# Powerboard.net
KiCad netlist of a schematic drawn in EAGLE
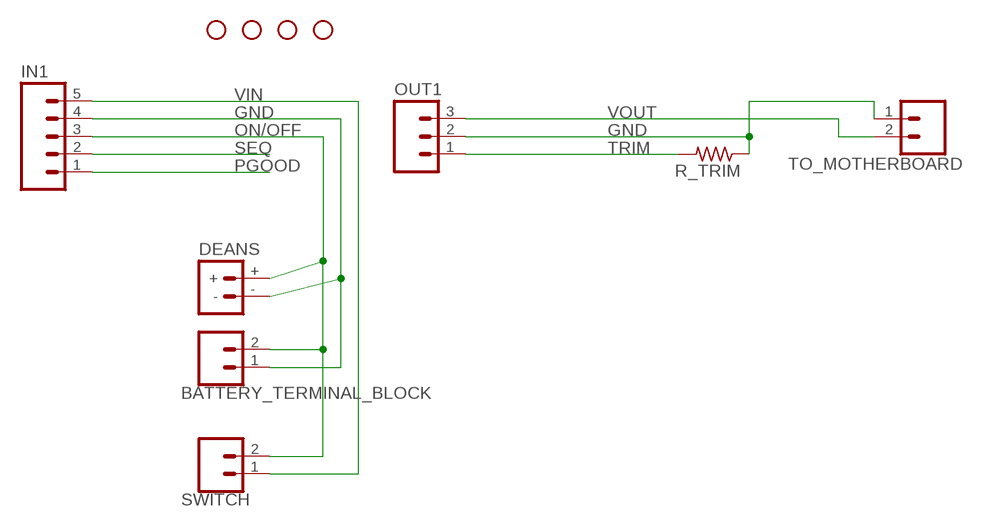
[diagram p0: schematic, sheet 1]

(export (version "E")
  (design (tool "Eeschema 10.0.6"))
  (components
    (comp (ref "BATTERY_TERMINAL_BLOCK")
      (value "CONN_023.5MM")
      (footprint "eagle-import:SCREWTERMINAL-3.5MM-2")
      (libsource (lib "eagle-import") (part "CONN_023.5MM"))
    )
    (comp (ref "DEANS")
      (value "BATTERY_CONN_DEANS")
      (footprint "eagle-import:DEANS")
      (libsource (lib "eagle-import") (part "BATTERY_CONN_DEANS"))
    )
    (comp (ref "IN1")
      (value "M05PTH")
      (footprint "eagle-import:1X05")
      (libsource (lib "eagle-import") (part "M05PTH"))
    )
    (comp (ref "OUT1")
      (value "M03PTH")
      (footprint "eagle-import:1X03")
      (libsource (lib "eagle-import") (part "M03PTH"))
    )
    (comp (ref "R_TRIM")
      (value "R-US_R0603")
      (footprint "eagle-import:R0603")
      (libsource (lib "eagle-import") (part "R-US_R0603"))
    )
    (comp (ref "SWITCH")
      (value "CONN_023.5MM")
      (footprint "eagle-import:SCREWTERMINAL-3.5MM-2")
      (libsource (lib "eagle-import") (part "CONN_023.5MM"))
    )
    (comp (ref "TO_MOTHERBOARD")
      (value "CONN_023.5MM")
      (footprint "eagle-import:SCREWTERMINAL-3.5MM-2")
      (libsource (lib "eagle-import") (part "CONN_023.5MM"))
    )
    (comp (ref "U$2")
      (value "STAND-OFF")
      (footprint "eagle-import:STAND-OFF")
      (libsource (lib "eagle-import") (part "STAND-OFF"))
    )
    (comp (ref "U$6")
      (value "STAND-OFF")
      (footprint "eagle-import:STAND-OFF")
      (libsource (lib "eagle-import") (part "STAND-OFF"))
    )
    (comp (ref "U$7")
      (value "STAND-OFF")
      (footprint "eagle-import:STAND-OFF")
      (libsource (lib "eagle-import") (part "STAND-OFF"))
    )
    (comp (ref "U$8")
      (value "STAND-OFF")
      (footprint "eagle-import:STAND-OFF")
      (libsource (lib "eagle-import") (part "STAND-OFF"))
    )
  )
  (nets
    (net (code "1") (name "/GND") (class "Default")
      (node (ref "BATTERY_TERMINAL_BLOCK") (pin "1") (pinfunction "1_1") (pintype "passive"))
      (node (ref "DEANS") (pin "-") (pinfunction "-_-") (pintype "passive"))
      (node (ref "IN1") (pin "4") (pinfunction "4_4") (pintype "passive"))
      (node (ref "OUT1") (pin "2") (pinfunction "2_2") (pintype "passive"))
      (node (ref "R_TRIM") (pin "1") (pinfunction "1_1") (pintype "passive"))
      (node (ref "TO_MOTHERBOARD") (pin "1") (pinfunction "1_1") (pintype "passive"))
    )
    (net (code "2") (name "/ON{slash}OFF") (class "Default")
      (node (ref "BATTERY_TERMINAL_BLOCK") (pin "2") (pinfunction "2_2") (pintype "passive"))
      (node (ref "DEANS") (pin "+") (pinfunction "+_+") (pintype "passive"))
      (node (ref "IN1") (pin "3") (pinfunction "3_3") (pintype "passive"))
      (node (ref "SWITCH") (pin "2") (pinfunction "2_2") (pintype "passive"))
    )
    (net (code "3") (name "/PGOOD") (class "Default")
      (node (ref "IN1") (pin "1") (pinfunction "1_1") (pintype "passive"))
    )
    (net (code "4") (name "/SEQ") (class "Default")
      (node (ref "IN1") (pin "2") (pinfunction "2_2") (pintype "passive"))
    )
    (net (code "5") (name "/TRIM") (class "Default")
      (node (ref "OUT1") (pin "1") (pinfunction "1_1") (pintype "passive"))
      (node (ref "R_TRIM") (pin "2") (pinfunction "2_2") (pintype "passive"))
    )
    (net (code "6") (name "/VIN") (class "Default")
      (node (ref "IN1") (pin "5") (pinfunction "5_5") (pintype "passive"))
      (node (ref "SWITCH") (pin "1") (pinfunction "1_1") (pintype "passive"))
    )
    (net (code "7") (name "/VOUT") (class "Default")
      (node (ref "OUT1") (pin "3") (pinfunction "3_3") (pintype "passive"))
      (node (ref "TO_MOTHERBOARD") (pin "2") (pinfunction "2_2") (pintype "passive"))
    )
  )
)
